# RAM_and_target_USB.net
KiCad netlist of a schematic drawn in Altium Designer
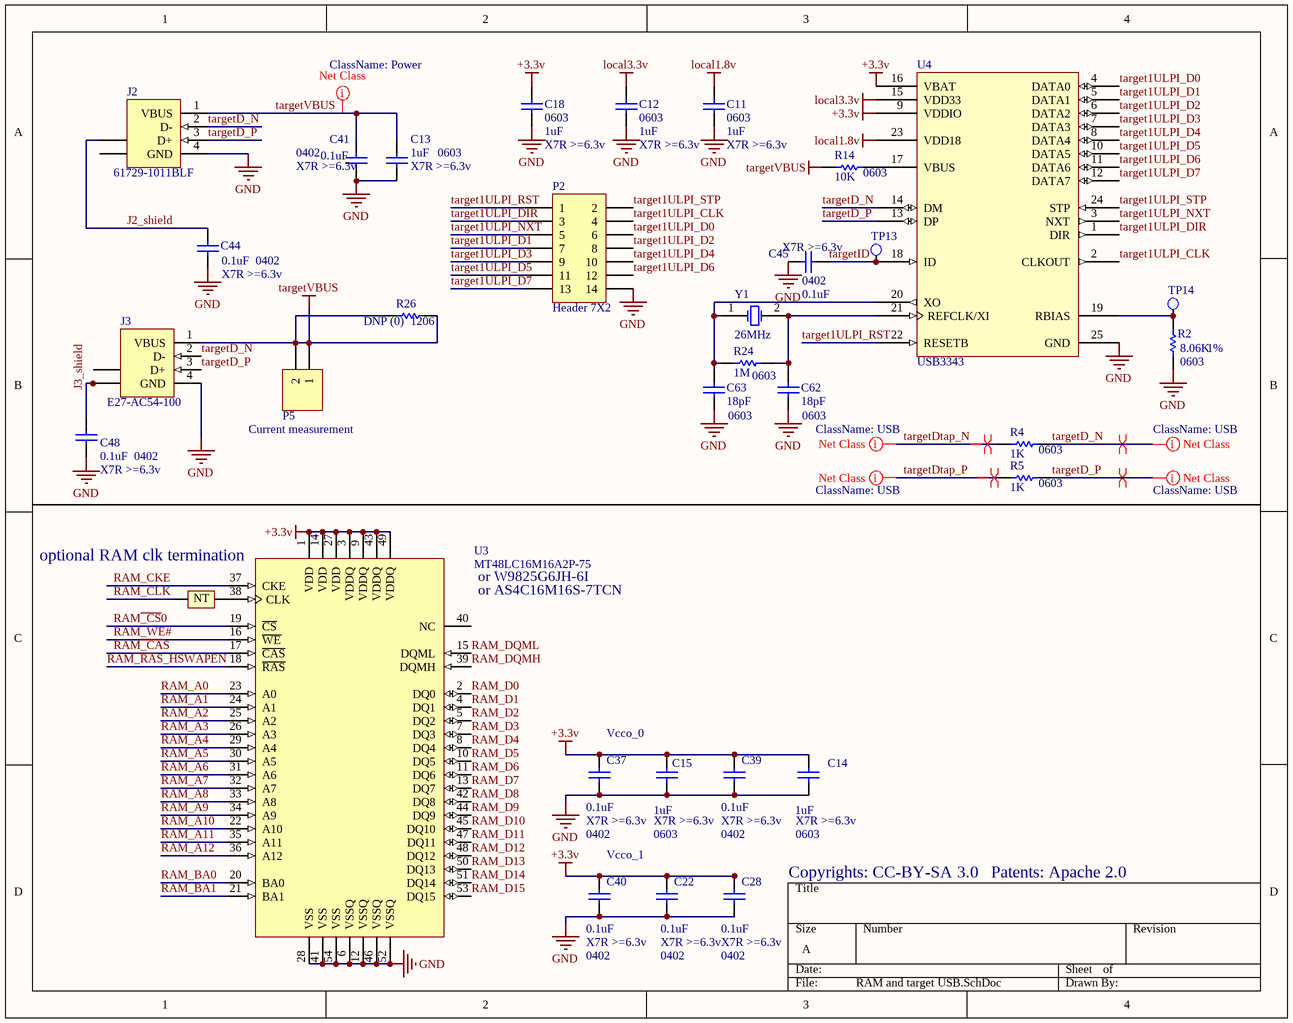
[diagram p0: RAM and target USB.SchDoc]

(export (version "E")
  (design (tool "Eeschema 10.0.6"))
  (components
    (comp (ref "C11")
      (value "1uF")
      (footprint "Chip_Capacitor_N:CAPC1608N")
      (description "CAP CER 10000PF 6.3V X5R 0201")
      (fields
        (field (name "PACKAGEREFERENCE") "0603")
        (field (name "RATING") "X7R >=6.3v")
        (field (name "TOLERANCE") "±10%")
      )
      (libsource (lib "Miscellaneous Devices") (part "Cap Semi"))
    )
    (comp (ref "C12")
      (value "1uF")
      (footprint "Chip_Capacitor_N:CAPC1608N")
      (description "CAP CER 10000PF 6.3V X5R 0201")
      (fields
        (field (name "PACKAGEREFERENCE") "0603")
        (field (name "RATING") "X7R >=6.3v")
        (field (name "TOLERANCE") "±10%")
      )
      (libsource (lib "Miscellaneous Devices") (part "Cap Semi"))
    )
    (comp (ref "C13")
      (value "1uF")
      (footprint "Chip_Capacitor_N:CAPC1608N")
      (description "Capacitor (Semiconductor SIM Model)")
      (fields
        (field (name "PACKAGEREFERENCE") "0603")
        (field (name "RATING") "X7R >=6.3v")
        (field (name "Comment") "Cap Semi")
      )
      (libsource (lib "Miscellaneous Devices") (part "Cap Semi"))
    )
    (comp (ref "C14")
      (value "1uF")
      (footprint "Chip_Capacitor_N:CAPC1608N")
      (description "Capacitor (Semiconductor SIM Model)")
      (fields
        (field (name "PACKAGEREFERENCE") "0603")
        (field (name "RATING") "X7R >=6.3v")
        (field (name "Comment") "Cap Semi")
      )
      (libsource (lib "Miscellaneous Devices") (part "Cap Semi"))
    )
    (comp (ref "C15")
      (value "1uF")
      (footprint "Chip_Capacitor_N:CAPC1608N")
      (description "Capacitor (Semiconductor SIM Model)")
      (fields
        (field (name "PACKAGEREFERENCE") "0603")
        (field (name "RATING") "X7R >=6.3v")
        (field (name "Comment") "Cap Semi")
      )
      (libsource (lib "Miscellaneous Devices") (part "Cap Semi"))
    )
    (comp (ref "C18")
      (value "1uF")
      (footprint "Chip_Capacitor_N:CAPC1608N")
      (description "CAP CER 10000PF 6.3V X5R 0201")
      (fields
        (field (name "PACKAGEREFERENCE") "0603")
        (field (name "RATING") "X7R >=6.3v")
        (field (name "TOLERANCE") "±10%")
      )
      (libsource (lib "Miscellaneous Devices") (part "Cap Semi"))
    )
    (comp (ref "C22")
      (value "0.1uF")
      (footprint "CAPC1005N")
      (description "CAP CER 0.1UF 25V 10% X5R 0603")
      (fields
        (field (name "PACKAGEREFERENCE") "0402")
        (field (name "TOLERANCE") "±10%")
        (field (name "RATING") "X7R >=6.3v")
      )
      (libsource (lib "Miscellaneous Devices") (part "Cap Semi"))
    )
    (comp (ref "C28")
      (value "0.1uF")
      (footprint "CAPC1005N")
      (description "CAP CER 0.1UF 25V 10% X5R 0603")
      (fields
        (field (name "PACKAGEREFERENCE") "0402")
        (field (name "TOLERANCE") "±10%")
        (field (name "RATING") "X7R >=6.3v")
      )
      (libsource (lib "Miscellaneous Devices") (part "Cap Semi"))
    )
    (comp (ref "C37")
      (value "0.1uF")
      (footprint "CAPC1005N")
      (description "Capacitor (Semiconductor SIM Model)")
      (fields
        (field (name "PACKAGEREFERENCE") "0402")
        (field (name "RATING") "X7R >=6.3v")
        (field (name "TOLERANCE") "±10%")
        (field (name "Comment") "Cap Semi")
      )
      (libsource (lib "Miscellaneous Devices") (part "Cap Semi"))
    )
    (comp (ref "C39")
      (value "0.1uF")
      (footprint "CAPC1005N")
      (description "Capacitor (Semiconductor SIM Model)")
      (fields
        (field (name "PACKAGEREFERENCE") "0402")
        (field (name "RATING") "X7R >=6.3v")
        (field (name "TOLERANCE") "±10%")
        (field (name "Comment") "Cap Semi")
      )
      (libsource (lib "Miscellaneous Devices") (part "Cap Semi"))
    )
    (comp (ref "C40")
      (value "0.1uF")
      (footprint "CAPC1005N")
      (description "CAP CER 0.1UF 25V 10% X5R 0603")
      (fields
        (field (name "PACKAGEREFERENCE") "0402")
        (field (name "TOLERANCE") "±10%")
        (field (name "RATING") "X7R >=6.3v")
      )
      (libsource (lib "Miscellaneous Devices") (part "Cap Semi"))
    )
    (comp (ref "C41")
      (value "0.1uF")
      (footprint "CAPC1005N")
      (description "Capacitor (Semiconductor SIM Model)")
      (fields
        (field (name "PACKAGEREFERENCE") "0402")
        (field (name "RATING") "X7R >=6.3v")
        (field (name "TOLERANCE") "±10%")
        (field (name "Comment") "Cap Semi")
      )
      (libsource (lib "Miscellaneous Devices") (part "Cap Semi"))
    )
    (comp (ref "C44")
      (value "0.1uF")
      (footprint "CAPC1005N")
      (description "Capacitor (Semiconductor SIM Model)")
      (fields
        (field (name "PACKAGEREFERENCE") "0402")
        (field (name "RATING") "X7R >=6.3v")
        (field (name "TOLERANCE") "±10%")
        (field (name "Comment") "Cap Semi")
      )
      (libsource (lib "Miscellaneous Devices") (part "Cap Semi"))
    )
    (comp (ref "C45")
      (value "0.1uF")
      (footprint "CAPC1005N")
      (description "Capacitor (Semiconductor SIM Model)")
      (fields
        (field (name "PACKAGEREFERENCE") "0402")
        (field (name "RATING") "X7R >=6.3v")
        (field (name "TOLERANCE") "±10%")
        (field (name "Comment") "Cap Semi")
      )
      (libsource (lib "Miscellaneous Devices") (part "Cap Semi"))
    )
    (comp (ref "C48")
      (value "0.1uF")
      (footprint "CAPC1005N")
      (description "Capacitor (Semiconductor SIM Model)")
      (fields
        (field (name "PACKAGEREFERENCE") "0402")
        (field (name "RATING") "X7R >=6.3v")
        (field (name "TOLERANCE") "±10%")
        (field (name "Comment") "Cap Semi")
      )
      (libsource (lib "Miscellaneous Devices") (part "Cap Semi"))
    )
    (comp (ref "C62")
      (value "18pF")
      (footprint "Chip_Capacitor_N:CAPC1608N")
      (description "Capacitor (Semiconductor SIM Model)")
      (fields (field (name "PACKAGEREFERENCE") "0603") (field (name "Comment") "Cap Semi"))
      (libsource (lib "Miscellaneous Devices") (part "Cap Semi"))
    )
    (comp (ref "C63")
      (value "18pF")
      (footprint "Chip_Capacitor_N:CAPC1608N")
      (description "Capacitor (Semiconductor SIM Model)")
      (fields (field (name "PACKAGEREFERENCE") "0603") (field (name "Comment") "Cap Semi"))
      (libsource (lib "Miscellaneous Devices") (part "Cap Semi"))
    )
    (comp (ref "J2")
      (value "61729-1011BLF")
      (footprint "1-1470156")
      (description "USB 1.1, Right Angle, Thru-Hole, B Type, Receptacle, 4 Position, White")
      (fields (field (name "Comment") "1-1470156-1"))
      (libsource (lib "AMP Serial Bus USB") (part "1-1470156-1"))
    )
    (comp (ref "J3")
      (value "E27-AC54-100")
      (footprint "787616")
      (description "USB 1.1, Right Angle, Thru-Hole, A Type, Receptacle, 4 Position, Black")
      (fields (field (name "Comment") "787616-1"))
      (libsource (lib "AMP Serial Bus USB") (part "787616-1"))
    )
    (comp (ref "NT1")
      (value "Net Tie2")
      (footprint "NetTie 0603")
      (description "0603 Net Tie to connect 2 different nets")
      (libsource (lib "OpenVizsla symbols") (part "Net Tie2"))
    )
    (comp (ref "P2")
      (value "Header 7X2")
      (footprint "HDR2X7")
      (description "Header, 7-Pin, Dual row")
      (libsource (lib "Miscellaneous Connectors") (part "Header 7X2"))
    )
    (comp (ref "P5")
      (value "Current measurement")
      (footprint "HDR1X2")
      (description "Header, 2-Pin")
      (libsource (lib "Miscellaneous Connectors") (part "Header 2"))
    )
    (comp (ref "R2")
      (value "8.06K")
      (footprint "RESC1608N")
      (description "Semiconductor Resistor")
      (fields
        (field (name "PACKAGEREFERENCE") "0603")
        (field (name "RATING") "1%")
        (field (name "Comment") "Res Semi")
      )
      (libsource (lib "Miscellaneous Devices") (part "Res Semi"))
    )
    (comp (ref "R4")
      (value "1K")
      (footprint "RESC1608N")
      (description "Semiconductor Resistor")
      (fields (field (name "PACKAGEREFERENCE") "0603") (field (name "Comment") "Res Semi"))
      (libsource (lib "Miscellaneous Devices") (part "Res Semi"))
    )
    (comp (ref "R5")
      (value "1K")
      (footprint "RESC1608N")
      (description "Semiconductor Resistor")
      (fields (field (name "PACKAGEREFERENCE") "0603") (field (name "Comment") "Res Semi"))
      (libsource (lib "Miscellaneous Devices") (part "Res Semi"))
    )
    (comp (ref "R14")
      (value "10K")
      (footprint "RESC1608N")
      (description "Semiconductor Resistor")
      (fields (field (name "PACKAGEREFERENCE") "0603") (field (name "Comment") "Res Semi"))
      (libsource (lib "Miscellaneous Devices") (part "Res Semi"))
    )
    (comp (ref "R24")
      (value "1M")
      (footprint "RESC1608N")
      (description "Semiconductor Resistor")
      (fields (field (name "PACKAGEREFERENCE") "0603") (field (name "Comment") "Res Semi"))
      (libsource (lib "Miscellaneous Devices") (part "Res Semi"))
    )
    (comp (ref "R26")
      (value "DNP (0)")
      (footprint "RESC3216N")
      (description "Semiconductor Resistor")
      (fields (field (name "PACKAGEREFERENCE") "1206") (field (name "Comment") "Res Semi"))
      (libsource (lib "Miscellaneous Devices") (part "Res Semi"))
    )
    (comp (ref "TP13")
      (value "Test Point")
      (footprint "testpoint")
      (libsource (lib "OpenVizsla symbols") (part "Test Pad"))
    )
    (comp (ref "TP14")
      (value "Test Point")
      (footprint "testpoint")
      (libsource (lib "OpenVizsla symbols") (part "Test Pad"))
    )
    (comp (ref "U3")
      (value "MT48LC16M16A2P-75")
      (footprint "TSOP2-54_N")
      (description "256Mb Synchronous High-Speed CMOS DRAM, 16Mb x 16Bit x 4 Banks, 54-Pin TSOP Pb-free, Commercial")
      (libsource (lib "Micron Memory Dynamic RAM") (part "MT48LC16M16A2P-75"))
    )
    (comp (ref "U4")
      (value "USB3343")
      (footprint "SMSC USB334x QFN24")
      (description "Hi-Speed USB Transceiver with 1.8V-3.3V ULPI Interface - MHz Reference Clock")
      (libsource (lib "OpenVizsla symbols") (part "USB3343"))
    )
    (comp (ref "Y1")
      (value "26MHz")
      (footprint "HC49/4H_SMX")
      (description "Crystal Oscillator")
      (libsource (lib "Miscellaneous Devices") (part "XTAL"))
    )
  )
  (nets
    (net (code "1") (name "+3.3v") (class "Default")
      (node (ref "C14") (pin "2") (pinfunction "2_2") (pintype "passive"))
      (node (ref "C15") (pin "2") (pinfunction "2_2") (pintype "passive"))
      (node (ref "C18") (pin "1") (pinfunction "1_1") (pintype "passive"))
      (node (ref "C22") (pin "2") (pinfunction "2_2") (pintype "passive"))
      (node (ref "C28") (pin "2") (pinfunction "2_2") (pintype "passive"))
      (node (ref "C37") (pin "2") (pinfunction "2_2") (pintype "passive"))
      (node (ref "C39") (pin "2") (pinfunction "2_2") (pintype "passive"))
      (node (ref "C40") (pin "2") (pinfunction "2_2") (pintype "passive"))
      (node (ref "U3") (pin "1") (pinfunction "VDD_1") (pintype "power_in"))
      (node (ref "U3") (pin "14") (pinfunction "VDD_14") (pintype "power_in"))
      (node (ref "U3") (pin "27") (pinfunction "VDD_27") (pintype "power_in"))
      (node (ref "U3") (pin "3") (pinfunction "VDDQ_3") (pintype "power_in"))
      (node (ref "U3") (pin "43") (pinfunction "VDDQ_43") (pintype "power_in"))
      (node (ref "U3") (pin "49") (pinfunction "VDDQ_49") (pintype "power_in"))
      (node (ref "U3") (pin "9") (pinfunction "VDDQ_9") (pintype "power_in"))
      (node (ref "U4") (pin "16") (pinfunction "VBAT_16") (pintype "power_in"))
      (node (ref "U4") (pin "9") (pinfunction "VDDIO_9") (pintype "power_in"))
    )
    (net (code "2") (name "/J2_shield") (class "Default")
      (node (ref "C44") (pin "2") (pinfunction "2_2") (pintype "passive"))
      (node (ref "J2") (pin "5") (pinfunction "SHLD_5") (pintype "passive"))
    )
    (net (code "3") (name "/J3_shield") (class "Default")
      (node (ref "C48") (pin "2") (pinfunction "2_2") (pintype "passive"))
      (node (ref "J3") (pin "6") (pinfunction "SHLD_6") (pintype "passive"))
    )
    (net (code "4") (name "/RAM_A0") (class "Default")
      (node (ref "U3") (pin "23") (pinfunction "A0_23") (pintype "input"))
    )
    (net (code "5") (name "/RAM_A1") (class "Default")
      (node (ref "U3") (pin "24") (pinfunction "A1_24") (pintype "input"))
    )
    (net (code "6") (name "/RAM_A2") (class "Default")
      (node (ref "U3") (pin "25") (pinfunction "A2_25") (pintype "input"))
    )
    (net (code "7") (name "/RAM_A3") (class "Default")
      (node (ref "U3") (pin "26") (pinfunction "A3_26") (pintype "input"))
    )
    (net (code "8") (name "/RAM_A4") (class "Default")
      (node (ref "U3") (pin "29") (pinfunction "A4_29") (pintype "input"))
    )
    (net (code "9") (name "/RAM_A5") (class "Default")
      (node (ref "U3") (pin "30") (pinfunction "A5_30") (pintype "input"))
    )
    (net (code "10") (name "/RAM_A6") (class "Default")
      (node (ref "U3") (pin "31") (pinfunction "A6_31") (pintype "input"))
    )
    (net (code "11") (name "/RAM_A7") (class "Default")
      (node (ref "U3") (pin "32") (pinfunction "A7_32") (pintype "input"))
    )
    (net (code "12") (name "/RAM_A8") (class "Default")
      (node (ref "U3") (pin "33") (pinfunction "A8_33") (pintype "input"))
    )
    (net (code "13") (name "/RAM_A9") (class "Default")
      (node (ref "U3") (pin "34") (pinfunction "A9_34") (pintype "input"))
    )
    (net (code "14") (name "/RAM_A10") (class "Default")
      (node (ref "U3") (pin "22") (pinfunction "A10_22") (pintype "input"))
    )
    (net (code "15") (name "/RAM_A11") (class "Default")
      (node (ref "U3") (pin "35") (pinfunction "A11_35") (pintype "input"))
    )
    (net (code "16") (name "/RAM_A12") (class "Default")
      (node (ref "U3") (pin "36") (pinfunction "A12_36") (pintype "input"))
    )
    (net (code "17") (name "/RAM_BA0") (class "Default")
      (node (ref "U3") (pin "20") (pinfunction "BA0_20") (pintype "input"))
    )
    (net (code "18") (name "/RAM_BA1") (class "Default")
      (node (ref "U3") (pin "21") (pinfunction "BA1_21") (pintype "input"))
    )
    (net (code "19") (name "/RAM_CKE") (class "Default")
      (node (ref "U3") (pin "37") (pinfunction "CKE_37") (pintype "input"))
    )
    (net (code "20") (name "/RAM_CLK") (class "Default")
      (node (ref "NT1") (pin "1") (pinfunction "1_1") (pintype "passive"))
    )
    (net (code "21") (name "/RAM_D0") (class "Default")
      (node (ref "U3") (pin "2") (pinfunction "DQ0_2") (pintype "bidirectional"))
    )
    (net (code "22") (name "/RAM_D1") (class "Default")
      (node (ref "U3") (pin "4") (pinfunction "DQ1_4") (pintype "bidirectional"))
    )
    (net (code "23") (name "/RAM_D2") (class "Default")
      (node (ref "U3") (pin "5") (pinfunction "DQ2_5") (pintype "bidirectional"))
    )
    (net (code "24") (name "/RAM_D3") (class "Default")
      (node (ref "U3") (pin "7") (pinfunction "DQ3_7") (pintype "bidirectional"))
    )
    (net (code "25") (name "/RAM_D4") (class "Default")
      (node (ref "U3") (pin "8") (pinfunction "DQ4_8") (pintype "bidirectional"))
    )
    (net (code "26") (name "/RAM_D5") (class "Default")
      (node (ref "U3") (pin "10") (pinfunction "DQ5_10") (pintype "bidirectional"))
    )
    (net (code "27") (name "/RAM_D6") (class "Default")
      (node (ref "U3") (pin "11") (pinfunction "DQ6_11") (pintype "bidirectional"))
    )
    (net (code "28") (name "/RAM_D7") (class "Default")
      (node (ref "U3") (pin "13") (pinfunction "DQ7_13") (pintype "bidirectional"))
    )
    (net (code "29") (name "/RAM_D8") (class "Default")
      (node (ref "U3") (pin "42") (pinfunction "DQ8_42") (pintype "bidirectional"))
    )
    (net (code "30") (name "/RAM_D9") (class "Default")
      (node (ref "U3") (pin "44") (pinfunction "DQ9_44") (pintype "bidirectional"))
    )
    (net (code "31") (name "/RAM_D10") (class "Default")
      (node (ref "U3") (pin "45") (pinfunction "DQ10_45") (pintype "bidirectional"))
    )
    (net (code "32") (name "/RAM_D11") (class "Default")
      (node (ref "U3") (pin "47") (pinfunction "DQ11_47") (pintype "bidirectional"))
    )
    (net (code "33") (name "/RAM_D12") (class "Default")
      (node (ref "U3") (pin "48") (pinfunction "DQ12_48") (pintype "bidirectional"))
    )
    (net (code "34") (name "/RAM_D13") (class "Default")
      (node (ref "U3") (pin "50") (pinfunction "DQ13_50") (pintype "bidirectional"))
    )
    (net (code "35") (name "/RAM_D14") (class "Default")
      (node (ref "U3") (pin "51") (pinfunction "DQ14_51") (pintype "bidirectional"))
    )
    (net (code "36") (name "/RAM_D15") (class "Default")
      (node (ref "U3") (pin "53") (pinfunction "DQ15_53") (pintype "bidirectional"))
    )
    (net (code "37") (name "/RAM_DQMH") (class "Default")
      (node (ref "U3") (pin "39") (pinfunction "DQMH_39") (pintype "input"))
    )
    (net (code "38") (name "/RAM_DQML") (class "Default")
      (node (ref "U3") (pin "15") (pinfunction "DQML_15") (pintype "input"))
    )
    (net (code "39") (name "/RAM_WE#") (class "Default")
      (node (ref "U3") (pin "16") (pinfunction "~{WE}_16") (pintype "input"))
    )
    (net (code "40") (name "/RAM~{_CA}S") (class "Default")
      (node (ref "U3") (pin "17") (pinfunction "~{CAS}_17") (pintype "input"))
    )
    (net (code "41") (name "/RAM~{_CS}0") (class "Default")
      (node (ref "U3") (pin "19") (pinfunction "~{CS}_19") (pintype "input"))
    )
    (net (code "42") (name "/RAM~{_RA}S_HSWAPEN") (class "Default")
      (node (ref "U3") (pin "18") (pinfunction "~{RAS}_18") (pintype "input"))
    )
    (net (code "43") (name "/target1ULPI_CLK") (class "Default")
      (node (ref "P2") (pin "4") (pinfunction "4_4") (pintype "passive"))
      (node (ref "U4") (pin "2") (pinfunction "CLKOUT_2") (pintype "output"))
    )
    (net (code "44") (name "/target1ULPI_D0") (class "Default")
      (node (ref "P2") (pin "6") (pinfunction "6_6") (pintype "passive"))
      (node (ref "U4") (pin "4") (pinfunction "DATA0_4") (pintype "bidirectional"))
    )
    (net (code "45") (name "/target1ULPI_D1") (class "Default")
      (node (ref "P2") (pin "7") (pinfunction "7_7") (pintype "passive"))
      (node (ref "U4") (pin "5") (pinfunction "DATA1_5") (pintype "bidirectional"))
    )
    (net (code "46") (name "/target1ULPI_D2") (class "Default")
      (node (ref "P2") (pin "8") (pinfunction "8_8") (pintype "passive"))
      (node (ref "U4") (pin "6") (pinfunction "DATA2_6") (pintype "bidirectional"))
    )
    (net (code "47") (name "/target1ULPI_D3") (class "Default")
      (node (ref "P2") (pin "9") (pinfunction "9_9") (pintype "passive"))
      (node (ref "U4") (pin "7") (pinfunction "DATA3_7") (pintype "bidirectional"))
    )
    (net (code "48") (name "/target1ULPI_D4") (class "Default")
      (node (ref "P2") (pin "10") (pinfunction "10_10") (pintype "passive"))
      (node (ref "U4") (pin "8") (pinfunction "DATA4_8") (pintype "bidirectional"))
    )
    (net (code "49") (name "/target1ULPI_D5") (class "Default")
      (node (ref "P2") (pin "11") (pinfunction "11_11") (pintype "passive"))
      (node (ref "U4") (pin "10") (pinfunction "DATA5_10") (pintype "bidirectional"))
    )
    (net (code "50") (name "/target1ULPI_D6") (class "Default")
      (node (ref "P2") (pin "12") (pinfunction "12_12") (pintype "passive"))
      (node (ref "U4") (pin "11") (pinfunction "DATA6_11") (pintype "bidirectional"))
    )
    (net (code "51") (name "/target1ULPI_D7") (class "Default")
      (node (ref "P2") (pin "13") (pinfunction "13_13") (pintype "passive"))
      (node (ref "U4") (pin "12") (pinfunction "DATA7_12") (pintype "bidirectional"))
    )
    (net (code "52") (name "/target1ULPI_DIR") (class "Default")
      (node (ref "P2") (pin "3") (pinfunction "3_3") (pintype "passive"))
      (node (ref "U4") (pin "1") (pinfunction "DIR_1") (pintype "output"))
    )
    (net (code "53") (name "/target1ULPI_NXT") (class "Default")
      (node (ref "P2") (pin "5") (pinfunction "5_5") (pintype "passive"))
      (node (ref "U4") (pin "3") (pinfunction "NXT_3") (pintype "output"))
    )
    (net (code "54") (name "/target1ULPI_RST") (class "Default")
      (node (ref "P2") (pin "1") (pinfunction "1_1") (pintype "passive"))
      (node (ref "U4") (pin "22") (pinfunction "RESETB_22") (pintype "input"))
    )
    (net (code "55") (name "/target1ULPI_STP") (class "Default")
      (node (ref "P2") (pin "2") (pinfunction "2_2") (pintype "passive"))
      (node (ref "U4") (pin "24") (pinfunction "STP_24") (pintype "input"))
    )
    (net (code "56") (name "/targetD_N") (class "Default")
      (node (ref "J2") (pin "2") (pinfunction "D-_2") (pintype "input"))
      (node (ref "J3") (pin "2") (pinfunction "D-_2") (pintype "input"))
      (node (ref "R4") (pin "1") (pinfunction "1_1") (pintype "passive"))
      (node (ref "U4") (pin "14") (pinfunction "DM_14") (pintype "bidirectional"))
    )
    (net (code "57") (name "/targetD_P") (class "Default")
      (node (ref "J2") (pin "3") (pinfunction "D+_3") (pintype "input"))
      (node (ref "J3") (pin "3") (pinfunction "D+_3") (pintype "input"))
      (node (ref "R5") (pin "1") (pinfunction "1_1") (pintype "passive"))
      (node (ref "U4") (pin "13") (pinfunction "DP_13") (pintype "bidirectional"))
    )
    (net (code "58") (name "/targetDtap_N") (class "Default")
      (node (ref "R4") (pin "2") (pinfunction "2_2") (pintype "passive"))
    )
    (net (code "59") (name "/targetDtap_P") (class "Default")
      (node (ref "R5") (pin "2") (pinfunction "2_2") (pintype "passive"))
    )
    (net (code "60") (name "/targetID") (class "Default")
      (node (ref "C45") (pin "1") (pinfunction "1_1") (pintype "passive"))
      (node (ref "TP13") (pin "1") (pinfunction "pin_1") (pintype "passive"))
      (node (ref "U4") (pin "18") (pinfunction "ID_18") (pintype "input"))
    )
    (net (code "61") (name "GND") (class "Default")
      (node (ref "C11") (pin "2") (pinfunction "2_2") (pintype "passive"))
      (node (ref "C12") (pin "2") (pinfunction "2_2") (pintype "passive"))
      (node (ref "C13") (pin "1") (pinfunction "1_1") (pintype "passive"))
      (node (ref "C14") (pin "1") (pinfunction "1_1") (pintype "passive"))
      (node (ref "C15") (pin "1") (pinfunction "1_1") (pintype "passive"))
      (node (ref "C18") (pin "2") (pinfunction "2_2") (pintype "passive"))
      (node (ref "C22") (pin "1") (pinfunction "1_1") (pintype "passive"))
      (node (ref "C28") (pin "1") (pinfunction "1_1") (pintype "passive"))
      (node (ref "C37") (pin "1") (pinfunction "1_1") (pintype "passive"))
      (node (ref "C39") (pin "1") (pinfunction "1_1") (pintype "passive"))
      (node (ref "C40") (pin "1") (pinfunction "1_1") (pintype "passive"))
      (node (ref "C41") (pin "1") (pinfunction "1_1") (pintype "passive"))
      (node (ref "C44") (pin "1") (pinfunction "1_1") (pintype "passive"))
      (node (ref "C45") (pin "2") (pinfunction "2_2") (pintype "passive"))
      (node (ref "C48") (pin "1") (pinfunction "1_1") (pintype "passive"))
      (node (ref "C62") (pin "1") (pinfunction "1_1") (pintype "passive"))
      (node (ref "C63") (pin "1") (pinfunction "1_1") (pintype "passive"))
      (node (ref "J2") (pin "4") (pinfunction "GND_4") (pintype "power_in"))
      (node (ref "J3") (pin "4") (pinfunction "GND_4") (pintype "power_in"))
      (node (ref "P2") (pin "14") (pinfunction "14_14") (pintype "passive"))
      (node (ref "R2") (pin "1") (pinfunction "1_1") (pintype "passive"))
      (node (ref "U3") (pin "12") (pinfunction "VSSQ_12") (pintype "power_in"))
      (node (ref "U3") (pin "28") (pinfunction "VSS_28") (pintype "power_in"))
      (node (ref "U3") (pin "41") (pinfunction "VSS_41") (pintype "power_in"))
      (node (ref "U3") (pin "46") (pinfunction "VSSQ_46") (pintype "power_in"))
      (node (ref "U3") (pin "52") (pinfunction "VSSQ_52") (pintype "power_in"))
      (node (ref "U3") (pin "54") (pinfunction "VSS_54") (pintype "power_in"))
      (node (ref "U3") (pin "6") (pinfunction "VSSQ_6") (pintype "power_in"))
      (node (ref "U4") (pin "25") (pinfunction "GND_25") (pintype "power_in"))
    )
    (net (code "62") (name "Net-(TP14-pin)") (class "Default")
      (node (ref "R2") (pin "2") (pinfunction "2_2") (pintype "passive"))
      (node (ref "TP14") (pin "1") (pinfunction "pin_1") (pintype "passive"))
      (node (ref "U4") (pin "19") (pinfunction "RBIAS_19") (pintype "passive"))
    )
    (net (code "63") (name "Net-(U3-CLK)") (class "Default")
      (node (ref "NT1") (pin "2") (pinfunction "2_2") (pintype "passive"))
      (node (ref "U3") (pin "38") (pinfunction "CLK_38") (pintype "input"))
    )
    (net (code "64") (name "Net-(U4-REFCLK{slash}XI)") (class "Default")
      (node (ref "C62") (pin "2") (pinfunction "2_2") (pintype "passive"))
      (node (ref "R24") (pin "1") (pinfunction "1_1") (pintype "passive"))
      (node (ref "U4") (pin "21") (pinfunction "REFCLK/XI_21") (pintype "input"))
      (node (ref "Y1") (pin "2") (pinfunction "OSC2_2") (pintype "passive"))
    )
    (net (code "65") (name "Net-(U4-VBUS)") (class "Default")
      (node (ref "R14") (pin "1") (pinfunction "1_1") (pintype "passive"))
      (node (ref "U4") (pin "17") (pinfunction "VBUS_17") (pintype "power_in"))
    )
    (net (code "66") (name "Net-(U4-XO)") (class "Default")
      (node (ref "C63") (pin "2") (pinfunction "2_2") (pintype "passive"))
      (node (ref "R24") (pin "2") (pinfunction "2_2") (pintype "passive"))
      (node (ref "U4") (pin "20") (pinfunction "XO_20") (pintype "output"))
      (node (ref "Y1") (pin "1") (pinfunction "OSC1_1") (pintype "passive"))
    )
    (net (code "67") (name "local1.8v") (class "Default")
      (node (ref "C11") (pin "1") (pinfunction "1_1") (pintype "passive"))
      (node (ref "U4") (pin "23") (pinfunction "VDD18_23") (pintype "power_in"))
    )
    (net (code "68") (name "local3.3v") (class "Default")
      (node (ref "C12") (pin "1") (pinfunction "1_1") (pintype "passive"))
      (node (ref "U4") (pin "15") (pinfunction "VDD33_15") (pintype "power_in"))
    )
    (net (code "69") (name "targetVBUS") (class "Default")
      (node (ref "C13") (pin "2") (pinfunction "2_2") (pintype "passive"))
      (node (ref "C41") (pin "2") (pinfunction "2_2") (pintype "passive"))
      (node (ref "J2") (pin "1") (pinfunction "VBUS_1") (pintype "power_in"))
      (node (ref "J3") (pin "1") (pinfunction "VBUS_1") (pintype "power_in"))
      (node (ref "P5") (pin "1") (pinfunction "1_1") (pintype "passive"))
      (node (ref "P5") (pin "2") (pinfunction "2_2") (pintype "passive"))
      (node (ref "R14") (pin "2") (pinfunction "2_2") (pintype "passive"))
      (node (ref "R26") (pin "1") (pinfunction "1_1") (pintype "passive"))
      (node (ref "R26") (pin "2") (pinfunction "2_2") (pintype "passive"))
    )
    (net (code "70") (name "unconnected-(J2-SHLD-Pad6)") (class "Default")
      (node (ref "J2") (pin "6") (pinfunction "SHLD_6") (pintype "passive"))
    )
    (net (code "71") (name "unconnected-(J3-SHLD-Pad5)") (class "Default")
      (node (ref "J3") (pin "5") (pinfunction "SHLD_5") (pintype "passive"))
    )
    (net (code "72") (name "unconnected-(U3-NC-Pad40)") (class "Default")
      (node (ref "U3") (pin "40") (pinfunction "NC_40") (pintype "passive"))
    )
  )
)
